# tx_uts_wafer1.net
KiCad netlist of a schematic drawn in EAGLE
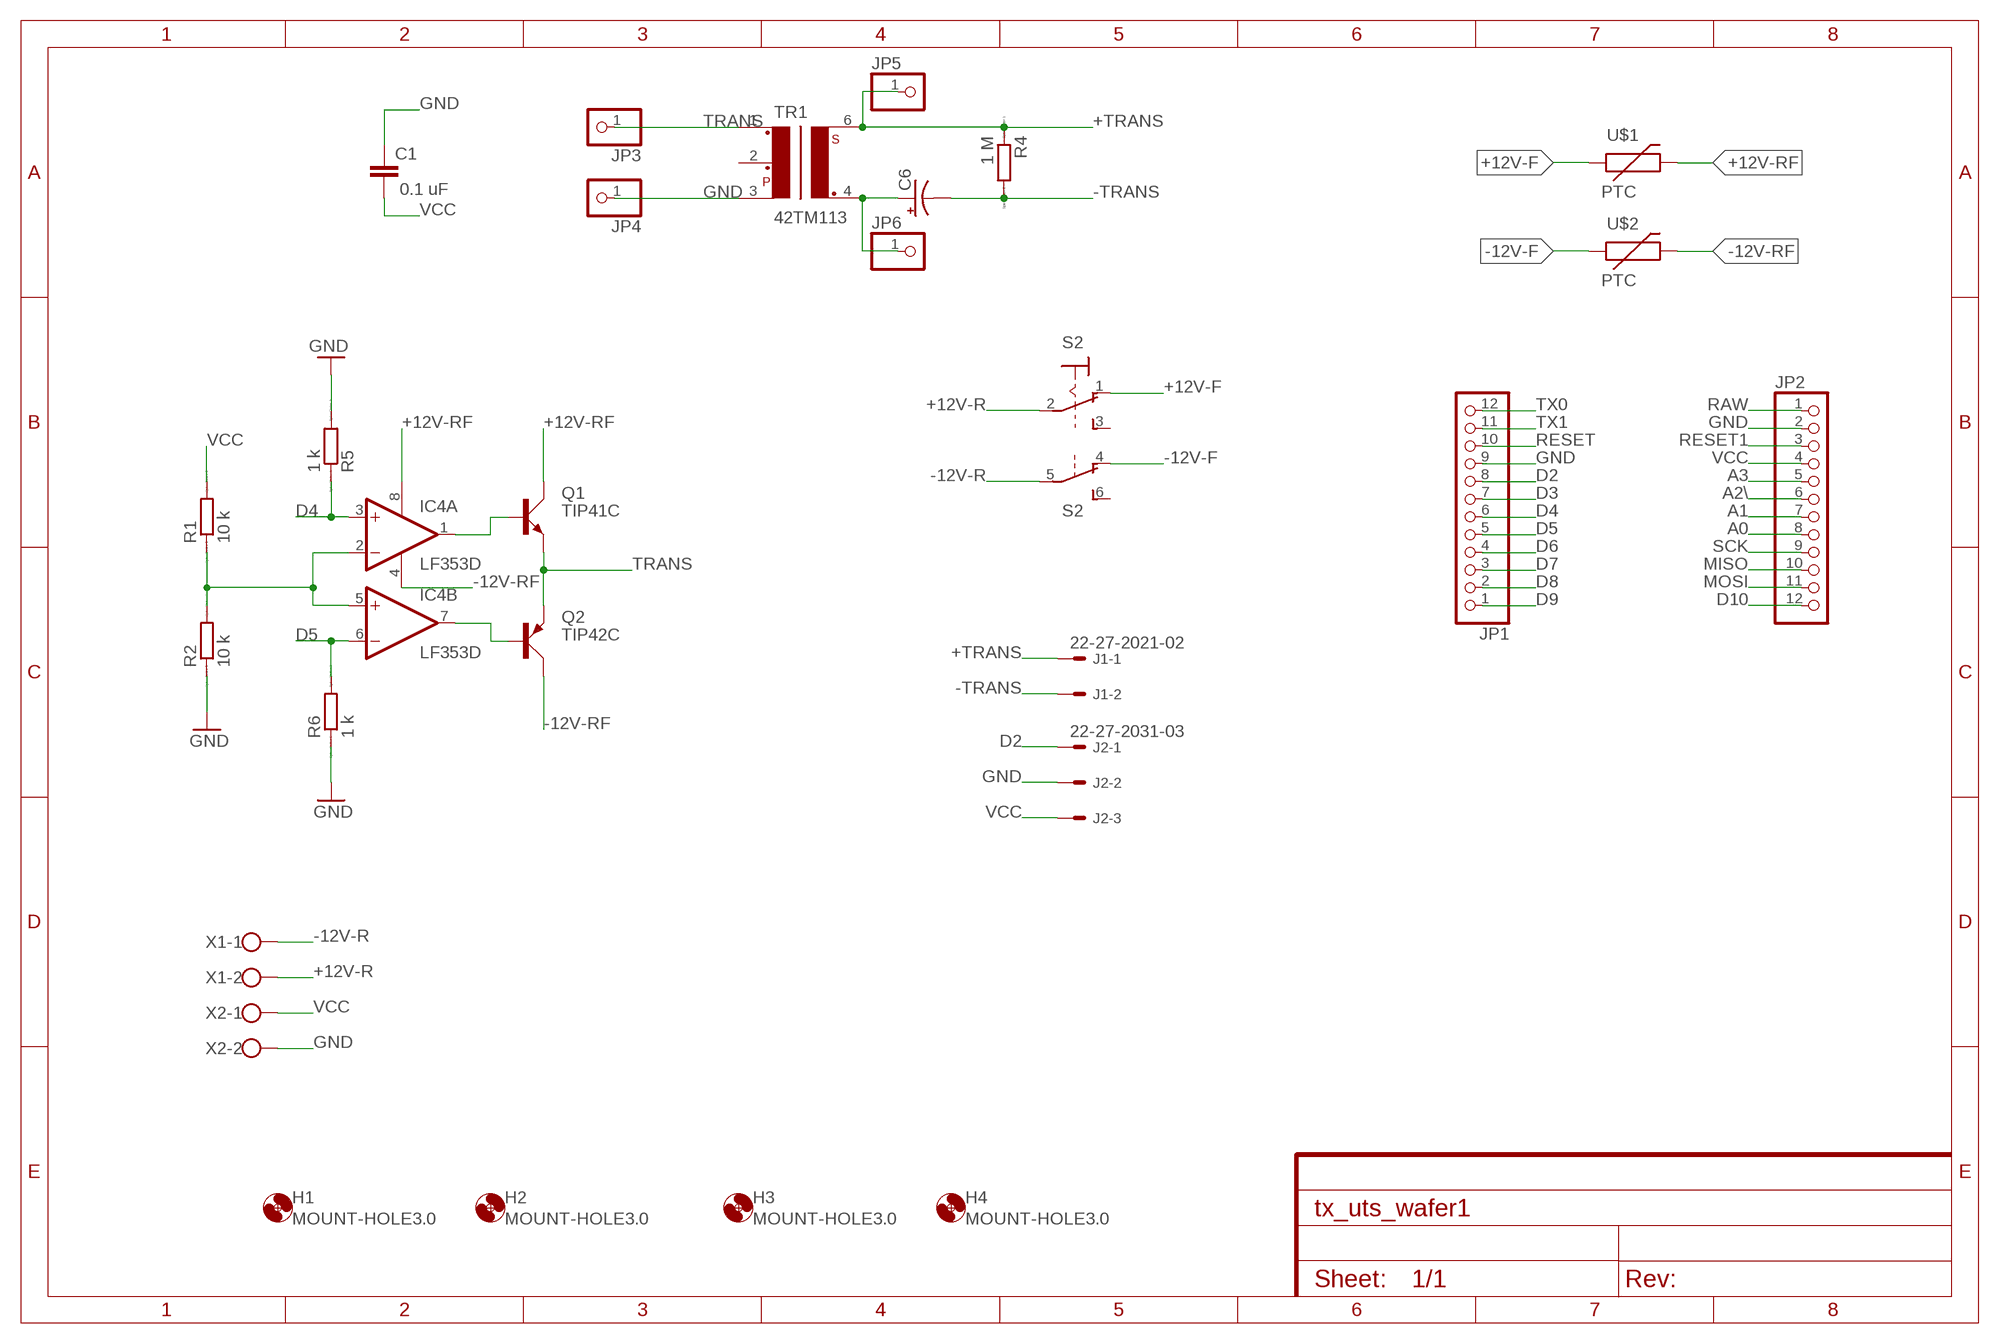
[diagram p0: schematic, sheet 1]

(export (version "E")
  (design (tool "Eeschema 10.0.6"))
  (components
    (comp (ref "C1")
      (value "0.1 uF")
      (footprint "eagle-import:C0603")
      (libsource (lib "eagle-import") (part "C-EUC0603"))
    )
    (comp (ref "C6")
      (value "CAP_POLC")
      (footprint "eagle-import:PANASONIC_C")
      (libsource (lib "eagle-import") (part "CAP_POLC"))
    )
    (comp (ref "H1")
      (value "MOUNT-HOLE3.0")
      (footprint "eagle-import:3,0")
      (libsource (lib "eagle-import") (part "MOUNT-HOLE3.0"))
    )
    (comp (ref "H2")
      (value "MOUNT-HOLE3.0")
      (footprint "eagle-import:3,0")
      (libsource (lib "eagle-import") (part "MOUNT-HOLE3.0"))
    )
    (comp (ref "H3")
      (value "MOUNT-HOLE3.0")
      (footprint "eagle-import:3,0")
      (libsource (lib "eagle-import") (part "MOUNT-HOLE3.0"))
    )
    (comp (ref "H4")
      (value "MOUNT-HOLE3.0")
      (footprint "eagle-import:3,0")
      (libsource (lib "eagle-import") (part "MOUNT-HOLE3.0"))
    )
    (comp (ref "IC4")
      (value "LF353D")
      (footprint "eagle-import:SO08")
      (libsource (lib "eagle-import") (part "LF353D"))
    )
    (comp (ref "J1")
      (value "22-27-2021-02")
      (footprint "eagle-import:6410-02")
      (libsource (lib "eagle-import") (part "22-?-0227-2021"))
    )
    (comp (ref "J2")
      (value "22-27-2031-03")
      (footprint "eagle-import:6410-03")
      (libsource (lib "eagle-import") (part "22-?-0327-2031"))
    )
    (comp (ref "JP1")
      (value "PINHD-1X12")
      (footprint "eagle-import:1X12")
      (libsource (lib "eagle-import") (part "PINHD-1X12"))
    )
    (comp (ref "JP2")
      (value "PINHD-1X12")
      (footprint "eagle-import:1X12")
      (libsource (lib "eagle-import") (part "PINHD-1X12"))
    )
    (comp (ref "JP3")
      (value "PINHD-1X1")
      (footprint "eagle-import:1X01")
      (libsource (lib "eagle-import") (part "PINHD-1X1"))
    )
    (comp (ref "JP4")
      (value "PINHD-1X1")
      (footprint "eagle-import:1X01")
      (libsource (lib "eagle-import") (part "PINHD-1X1"))
    )
    (comp (ref "JP5")
      (value "PINHD-1X1")
      (footprint "eagle-import:1X01")
      (libsource (lib "eagle-import") (part "PINHD-1X1"))
    )
    (comp (ref "JP6")
      (value "PINHD-1X1")
      (footprint "eagle-import:1X01")
      (libsource (lib "eagle-import") (part "PINHD-1X1"))
    )
    (comp (ref "Q1")
      (value "TIP41C")
      (footprint "eagle-import:TO220AV")
      (libsource (lib "eagle-import") (part "TIP41C"))
    )
    (comp (ref "Q2")
      (value "TIP42C")
      (footprint "eagle-import:TO220AV")
      (libsource (lib "eagle-import") (part "TIP42C"))
    )
    (comp (ref "R1")
      (value "10 k")
      (footprint "eagle-import:R0603")
      (libsource (lib "eagle-import") (part "RR0603"))
    )
    (comp (ref "R2")
      (value "10 k")
      (footprint "eagle-import:R0603")
      (libsource (lib "eagle-import") (part "RR0603"))
    )
    (comp (ref "R4")
      (value "1 M")
      (footprint "eagle-import:R0603")
      (libsource (lib "eagle-import") (part "RR0603"))
    )
    (comp (ref "R5")
      (value "1 k")
      (footprint "eagle-import:R0603")
      (libsource (lib "eagle-import") (part "RR0603"))
    )
    (comp (ref "R6")
      (value "1 k")
      (footprint "eagle-import:R0603")
      (libsource (lib "eagle-import") (part "RR0603"))
    )
    (comp (ref "S2")
      (value "M9040P2")
      (footprint "eagle-import:M9040P2")
      (libsource (lib "eagle-import") (part "M9040P2"))
    )
    (comp (ref "TR1")
      (value "42TM113")
      (footprint "eagle-import:42TM")
      (libsource (lib "eagle-import") (part "42TM113"))
    )
    (comp (ref "U$1")
      (value "PTC")
      (footprint "eagle-import:MC331XX")
      (libsource (lib "eagle-import") (part "PTC"))
    )
    (comp (ref "U$2")
      (value "PTC")
      (footprint "eagle-import:MC331XX")
      (libsource (lib "eagle-import") (part "PTC"))
    )
    (comp (ref "X1")
      (value "W237-102")
      (footprint "eagle-import:W237-102")
      (fields (field (name "MPN") "237-102"))
      (libsource (lib "eagle-import") (part "W237-102"))
    )
    (comp (ref "X2")
      (value "W237-102")
      (footprint "eagle-import:W237-102")
      (fields (field (name "MPN") "237-102"))
      (libsource (lib "eagle-import") (part "W237-102"))
    )
  )
  (nets
    (net (code "1") (name "+12V-F") (class "Default")
      (node (ref "S2") (pin "1") (pinfunction "O_1") (pintype "passive"))
      (node (ref "U$1") (pin "P$1") (pinfunction "1_P$1") (pintype "bidirectional"))
    )
    (net (code "2") (name "+12V-RF") (class "Default")
      (node (ref "IC4") (pin "8") (pinfunction "V+_8") (pintype "power_in"))
      (node (ref "Q1") (pin "C") (pinfunction "C_C") (pintype "passive"))
      (node (ref "U$1") (pin "P$2") (pinfunction "2_P$2") (pintype "bidirectional"))
    )
    (net (code "3") (name "-12V-F") (class "Default")
      (node (ref "S2") (pin "4") (pinfunction "O_4") (pintype "passive"))
      (node (ref "U$2") (pin "P$1") (pinfunction "1_P$1") (pintype "bidirectional"))
    )
    (net (code "4") (name "-12V-RF") (class "Default")
      (node (ref "IC4") (pin "4") (pinfunction "V-_4") (pintype "power_in"))
      (node (ref "Q2") (pin "C") (pinfunction "C_C") (pintype "passive"))
      (node (ref "U$2") (pin "P$2") (pinfunction "2_P$2") (pintype "bidirectional"))
    )
    (net (code "5") (name "/+12V-R") (class "Default")
      (node (ref "S2") (pin "2") (pinfunction "P_2") (pintype "passive"))
      (node (ref "X1") (pin "2") (pinfunction "KL_2") (pintype "passive"))
    )
    (net (code "6") (name "/+TRANS") (class "Default")
      (node (ref "J1") (pin "1") (pinfunction "S_1") (pintype "passive"))
      (node (ref "JP5") (pin "1") (pinfunction "1_1") (pintype "passive"))
      (node (ref "R4") (pin "1") (pinfunction "1_1") (pintype "passive"))
      (node (ref "TR1") (pin "6") (pinfunction "6_6") (pintype "passive"))
    )
    (net (code "7") (name "/-12V-R") (class "Default")
      (node (ref "S2") (pin "5") (pinfunction "P_5") (pintype "passive"))
      (node (ref "X1") (pin "1") (pinfunction "KL_1") (pintype "passive"))
    )
    (net (code "8") (name "/-TRANS") (class "Default")
      (node (ref "C6") (pin "-") (pinfunction "-_-") (pintype "passive"))
      (node (ref "J1") (pin "2") (pinfunction "S_2") (pintype "passive"))
      (node (ref "R4") (pin "2") (pinfunction "2_2") (pintype "passive"))
    )
    (net (code "9") (name "/A0") (class "Default")
      (node (ref "JP2") (pin "8") (pinfunction "8_8") (pintype "passive"))
    )
    (net (code "10") (name "/A1") (class "Default")
      (node (ref "JP2") (pin "7") (pinfunction "7_7") (pintype "passive"))
    )
    (net (code "11") (name "/A2\\") (class "Default")
      (node (ref "JP2") (pin "6") (pinfunction "6_6") (pintype "passive"))
    )
    (net (code "12") (name "/A3") (class "Default")
      (node (ref "JP2") (pin "5") (pinfunction "5_5") (pintype "passive"))
    )
    (net (code "13") (name "/D2") (class "Default")
      (node (ref "J2") (pin "1") (pinfunction "S_1") (pintype "passive"))
      (node (ref "JP1") (pin "8") (pinfunction "8_8") (pintype "passive"))
    )
    (net (code "14") (name "/D3") (class "Default")
      (node (ref "JP1") (pin "7") (pinfunction "7_7") (pintype "passive"))
    )
    (net (code "15") (name "/D4") (class "Default")
      (node (ref "IC4") (pin "3") (pinfunction "+IN_3") (pintype "input"))
      (node (ref "JP1") (pin "6") (pinfunction "6_6") (pintype "passive"))
      (node (ref "R5") (pin "1") (pinfunction "1_1") (pintype "passive"))
    )
    (net (code "16") (name "/D5") (class "Default")
      (node (ref "IC4") (pin "6") (pinfunction "-IN_6") (pintype "input"))
      (node (ref "JP1") (pin "5") (pinfunction "5_5") (pintype "passive"))
      (node (ref "R6") (pin "2") (pinfunction "2_2") (pintype "passive"))
    )
    (net (code "17") (name "/D6") (class "Default")
      (node (ref "JP1") (pin "4") (pinfunction "4_4") (pintype "passive"))
    )
    (net (code "18") (name "/D7") (class "Default")
      (node (ref "JP1") (pin "3") (pinfunction "3_3") (pintype "passive"))
    )
    (net (code "19") (name "/D8") (class "Default")
      (node (ref "JP1") (pin "2") (pinfunction "2_2") (pintype "passive"))
    )
    (net (code "20") (name "/D9") (class "Default")
      (node (ref "JP1") (pin "1") (pinfunction "1_1") (pintype "passive"))
    )
    (net (code "21") (name "/D10") (class "Default")
      (node (ref "JP2") (pin "12") (pinfunction "12_12") (pintype "passive"))
    )
    (net (code "22") (name "/MISO") (class "Default")
      (node (ref "JP2") (pin "10") (pinfunction "10_10") (pintype "passive"))
    )
    (net (code "23") (name "/MOSI") (class "Default")
      (node (ref "JP2") (pin "11") (pinfunction "11_11") (pintype "passive"))
    )
    (net (code "24") (name "/RAW") (class "Default")
      (node (ref "JP2") (pin "1") (pinfunction "1_1") (pintype "passive"))
    )
    (net (code "25") (name "/RESET") (class "Default")
      (node (ref "JP1") (pin "10") (pinfunction "10_10") (pintype "passive"))
    )
    (net (code "26") (name "/RESET1") (class "Default")
      (node (ref "JP2") (pin "3") (pinfunction "3_3") (pintype "passive"))
    )
    (net (code "27") (name "/SCK") (class "Default")
      (node (ref "JP2") (pin "9") (pinfunction "9_9") (pintype "passive"))
    )
    (net (code "28") (name "/TRANS") (class "Default")
      (node (ref "JP3") (pin "1") (pinfunction "1_1") (pintype "passive"))
      (node (ref "Q1") (pin "E") (pinfunction "E_E") (pintype "passive"))
      (node (ref "Q2") (pin "E") (pinfunction "E_E") (pintype "passive"))
      (node (ref "TR1") (pin "1") (pinfunction "1_1") (pintype "passive"))
    )
    (net (code "29") (name "/TX0") (class "Default")
      (node (ref "JP1") (pin "12") (pinfunction "12_12") (pintype "passive"))
    )
    (net (code "30") (name "/TX1") (class "Default")
      (node (ref "JP1") (pin "11") (pinfunction "11_11") (pintype "passive"))
    )
    (net (code "31") (name "/VCC") (class "Default")
      (node (ref "C1") (pin "2") (pinfunction "2_2") (pintype "passive"))
      (node (ref "J2") (pin "3") (pinfunction "S_3") (pintype "passive"))
      (node (ref "JP2") (pin "4") (pinfunction "4_4") (pintype "passive"))
      (node (ref "R1") (pin "2") (pinfunction "2_2") (pintype "passive"))
      (node (ref "X2") (pin "1") (pinfunction "KL_1") (pintype "passive"))
    )
    (net (code "32") (name "GND") (class "Default")
      (node (ref "C1") (pin "1") (pinfunction "1_1") (pintype "passive"))
      (node (ref "J2") (pin "2") (pinfunction "S_2") (pintype "passive"))
      (node (ref "JP1") (pin "9") (pinfunction "9_9") (pintype "passive"))
      (node (ref "JP2") (pin "2") (pinfunction "2_2") (pintype "passive"))
      (node (ref "JP4") (pin "1") (pinfunction "1_1") (pintype "passive"))
      (node (ref "R2") (pin "1") (pinfunction "1_1") (pintype "passive"))
      (node (ref "R5") (pin "2") (pinfunction "2_2") (pintype "passive"))
      (node (ref "R6") (pin "1") (pinfunction "1_1") (pintype "passive"))
      (node (ref "TR1") (pin "3") (pinfunction "3_3") (pintype "passive"))
      (node (ref "X2") (pin "2") (pinfunction "KL_2") (pintype "passive"))
    )
    (net (code "33") (name "Net-(C6-Pad+)") (class "Default")
      (node (ref "C6") (pin "+") (pinfunction "+_+") (pintype "passive"))
      (node (ref "JP6") (pin "1") (pinfunction "1_1") (pintype "passive"))
      (node (ref "TR1") (pin "4") (pinfunction "4_4") (pintype "passive"))
    )
    (net (code "34") (name "Net-(IC4A--IN)") (class "Default")
      (node (ref "IC4") (pin "2") (pinfunction "-IN_2") (pintype "input"))
      (node (ref "IC4") (pin "5") (pinfunction "+IN_5") (pintype "input"))
      (node (ref "R1") (pin "1") (pinfunction "1_1") (pintype "passive"))
      (node (ref "R2") (pin "2") (pinfunction "2_2") (pintype "passive"))
    )
    (net (code "35") (name "Net-(IC4A-OUT)") (class "Default")
      (node (ref "IC4") (pin "1") (pinfunction "OUT_1") (pintype "output"))
      (node (ref "Q1") (pin "B") (pinfunction "B_B") (pintype "passive"))
    )
    (net (code "36") (name "Net-(IC4B-OUT)") (class "Default")
      (node (ref "IC4") (pin "7") (pinfunction "OUT_7") (pintype "output"))
      (node (ref "Q2") (pin "B") (pinfunction "B_B") (pintype "passive"))
    )
    (net (code "37") (name "unconnected-(S2A-S-Pad3)") (class "Default")
      (node (ref "S2") (pin "3") (pinfunction "S_3") (pintype "passive"))
    )
    (net (code "38") (name "unconnected-(S2B-S-Pad6)") (class "Default")
      (node (ref "S2") (pin "6") (pinfunction "S_6") (pintype "passive"))
    )
    (net (code "39") (name "unconnected-(TR1-Pad2)") (class "Default")
      (node (ref "TR1") (pin "2") (pinfunction "2_2") (pintype "passive"))
    )
  )
)
